# FCCH_RFID_ESTOP.net
KiCad netlist of a schematic drawn in EAGLE
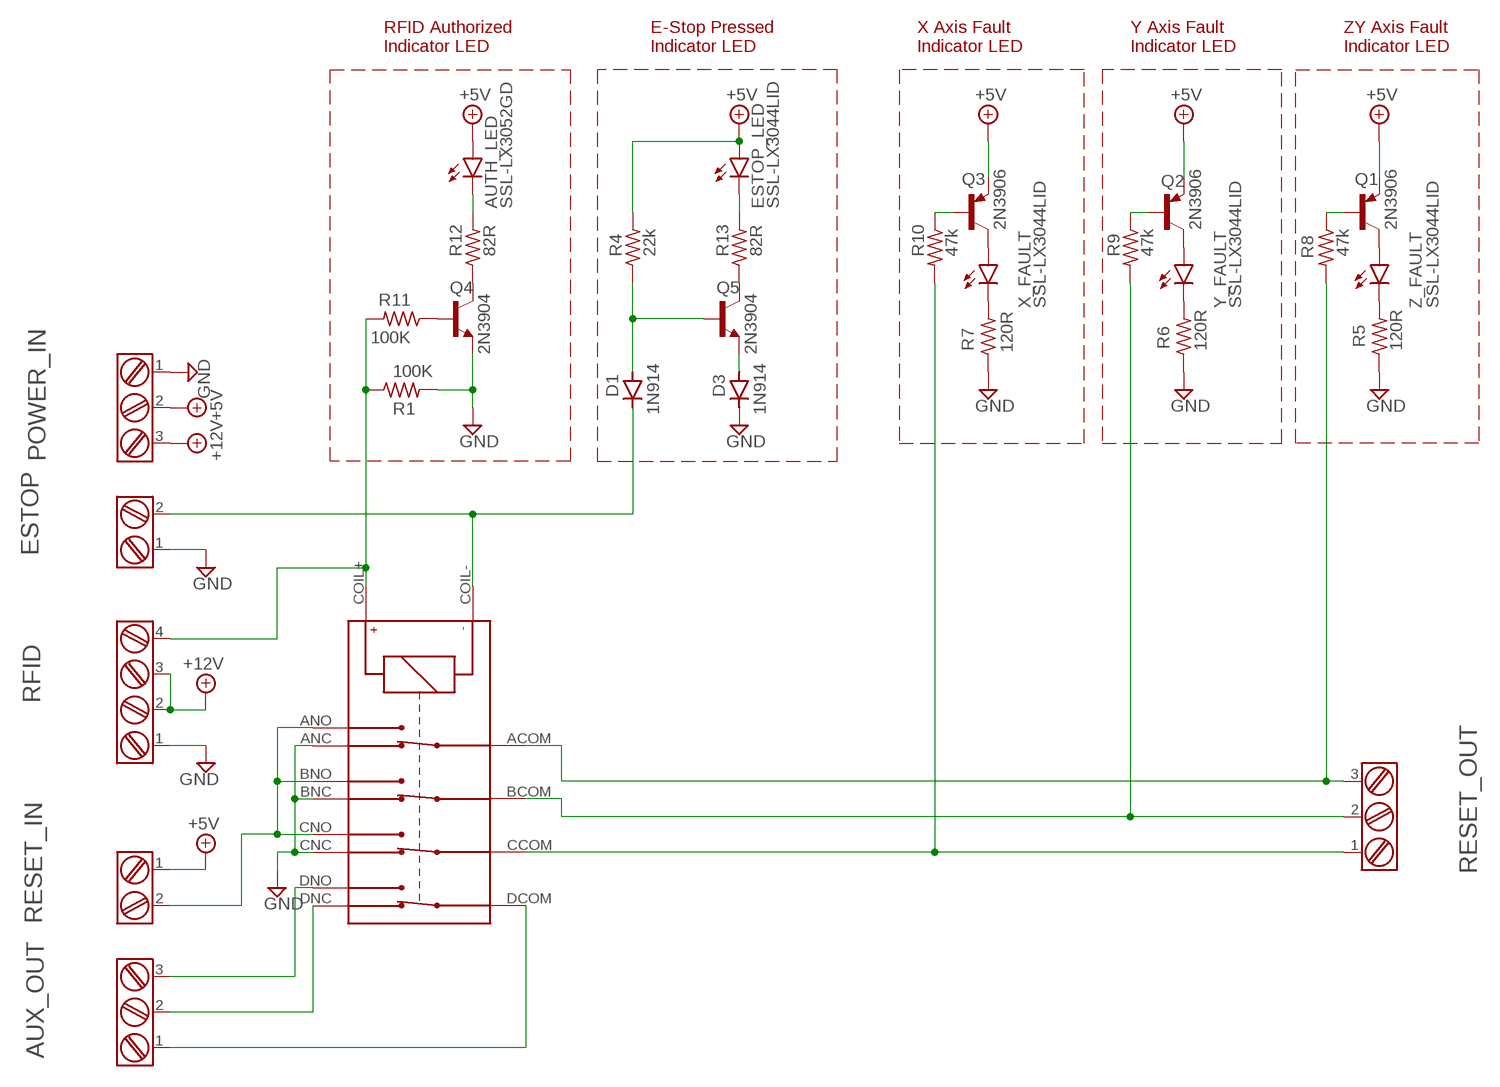
[diagram p0: schematic, sheet 1]

(export (version "E")
  (design (tool "Eeschema 10.0.6"))
  (components
    (comp (ref "AUTH_LED")
      (value "SSL-LX3052GD")
      (footprint "eagle-import:LED3MM")
      (libsource (lib "eagle-import") (part "LED3MM"))
    )
    (comp (ref "AUX_OUT")
      (value "EURO-CON-3_2.54P")
      (footprint "eagle-import:CONN3-2.54P")
      (fields
        (field (name "DIGIKEY_PART_NUMBER") "A98334-ND")
        (field (name "MF") "TE")
        (field (name "MOUSER_PART_NUMBER") "571-2828343")
      )
      (libsource (lib "eagle-import") (part "EURO-CON-3_2.54P"))
    )
    (comp (ref "D1")
      (value "1N914")
      (footprint "eagle-import:D-5")
      (libsource (lib "eagle-import") (part "DIODE-D-5"))
    )
    (comp (ref "D3")
      (value "1N914")
      (footprint "eagle-import:D-5")
      (libsource (lib "eagle-import") (part "DIODE-D-5"))
    )
    (comp (ref "ESTOP")
      (value "EURO-CON-2_2.54P")
      (footprint "eagle-import:CONN2_2.54P")
      (fields
        (field (name "DIGIKEY_PART_NUMBER") "A98333-ND")
        (field (name "MF") "TE")
        (field (name "MOUSER_PART_NUMBER") "571-282834-2")
      )
      (libsource (lib "eagle-import") (part "EURO-CON-2_2.54P"))
    )
    (comp (ref "ESTOP_LED")
      (value "SSL-LX3044LID")
      (footprint "eagle-import:LED3MM")
      (libsource (lib "eagle-import") (part "LED3MM"))
    )
    (comp (ref "POWER_IN")
      (value "EURO-CON-3_2.54P")
      (footprint "eagle-import:CONN3-2.54P")
      (fields
        (field (name "DIGIKEY_PART_NUMBER") "A98334-ND")
        (field (name "MF") "TE")
        (field (name "MOUSER_PART_NUMBER") "571-2828343")
      )
      (libsource (lib "eagle-import") (part "EURO-CON-3_2.54P"))
    )
    (comp (ref "Q1")
      (value "2N3906")
      (footprint "eagle-import:TO92")
      (libsource (lib "eagle-import") (part "2N3906"))
    )
    (comp (ref "Q2")
      (value "2N3906")
      (footprint "eagle-import:TO92")
      (libsource (lib "eagle-import") (part "2N3906"))
    )
    (comp (ref "Q3")
      (value "2N3906")
      (footprint "eagle-import:TO92")
      (libsource (lib "eagle-import") (part "2N3906"))
    )
    (comp (ref "Q4")
      (value "2N3904")
      (footprint "eagle-import:TO92")
      (libsource (lib "eagle-import") (part "2N3904"))
    )
    (comp (ref "Q5")
      (value "2N3904")
      (footprint "eagle-import:TO92")
      (libsource (lib "eagle-import") (part "2N3904"))
    )
    (comp (ref "R1")
      (value "100K")
      (footprint "eagle-import:0204_7")
      (libsource (lib "eagle-import") (part "R-US_0204/7"))
    )
    (comp (ref "R4")
      (value "22k")
      (footprint "eagle-import:0204_7")
      (libsource (lib "eagle-import") (part "R-US_0204/7"))
    )
    (comp (ref "R5")
      (value "120R")
      (footprint "eagle-import:0204_7")
      (libsource (lib "eagle-import") (part "R-US_0204/7"))
    )
    (comp (ref "R6")
      (value "120R")
      (footprint "eagle-import:0204_7")
      (libsource (lib "eagle-import") (part "R-US_0204/7"))
    )
    (comp (ref "R7")
      (value "120R")
      (footprint "eagle-import:0204_7")
      (libsource (lib "eagle-import") (part "R-US_0204/7"))
    )
    (comp (ref "R8")
      (value "47k")
      (footprint "eagle-import:0204_7")
      (libsource (lib "eagle-import") (part "R-US_0204/7"))
    )
    (comp (ref "R9")
      (value "47k")
      (footprint "eagle-import:0204_7")
      (libsource (lib "eagle-import") (part "R-US_0204/7"))
    )
    (comp (ref "R10")
      (value "47k")
      (footprint "eagle-import:0204_7")
      (libsource (lib "eagle-import") (part "R-US_0204/7"))
    )
    (comp (ref "R11")
      (value "100K")
      (footprint "eagle-import:0204_7")
      (libsource (lib "eagle-import") (part "R-US_0204/7"))
    )
    (comp (ref "R12")
      (value "82R")
      (footprint "eagle-import:0204_7")
      (libsource (lib "eagle-import") (part "R-US_0204/7"))
    )
    (comp (ref "R13")
      (value "82R")
      (footprint "eagle-import:0204_7")
      (libsource (lib "eagle-import") (part "R-US_0204/7"))
    )
    (comp (ref "RESET_IN")
      (value "EURO-CON-2_2.54P")
      (footprint "eagle-import:CONN2_2.54P")
      (fields
        (field (name "DIGIKEY_PART_NUMBER") "A98333-ND")
        (field (name "MF") "TE")
        (field (name "MOUSER_PART_NUMBER") "571-282834-2")
      )
      (libsource (lib "eagle-import") (part "EURO-CON-2_2.54P"))
    )
    (comp (ref "RESET_OUT")
      (value "EURO-CON-3_2.54P")
      (footprint "eagle-import:CONN3-2.54P")
      (fields
        (field (name "DIGIKEY_PART_NUMBER") "A98334-ND")
        (field (name "MF") "TE")
        (field (name "MOUSER_PART_NUMBER") "571-2828343")
      )
      (libsource (lib "eagle-import") (part "EURO-CON-3_2.54P"))
    )
    (comp (ref "RFID")
      (value "EURO-CON-4_2.54P")
      (footprint "eagle-import:CONN4-2.54P")
      (fields
        (field (name "DIGIKEY_PART_NUMBER") "A98335-ND")
        (field (name "MF") "TE")
        (field (name "MOUSER_PART_NUMBER") "571-282834-4")
      )
      (libsource (lib "eagle-import") (part "EURO-CON-4_2.54P"))
    )
    (comp (ref "U$1")
      (value "NC4D-JP-DC5V")
      (footprint "eagle-import:NC4D-JP")
      (libsource (lib "eagle-import") (part "NC4D-JP-DC5V"))
    )
    (comp (ref "X_FAULT")
      (value "SSL-LX3044LID")
      (footprint "eagle-import:LED3MM")
      (libsource (lib "eagle-import") (part "LED3MM"))
    )
    (comp (ref "Y_FAULT")
      (value "SSL-LX3044LID")
      (footprint "eagle-import:LED3MM")
      (libsource (lib "eagle-import") (part "LED3MM"))
    )
    (comp (ref "Z_FAULT")
      (value "SSL-LX3044LID")
      (footprint "eagle-import:LED3MM")
      (libsource (lib "eagle-import") (part "LED3MM"))
    )
  )
  (nets
    (net (code "1") (name "+5V") (class "Default")
      (node (ref "AUTH_LED") (pin "A") (pinfunction "A_A") (pintype "passive"))
      (node (ref "ESTOP_LED") (pin "A") (pinfunction "A_A") (pintype "passive"))
      (node (ref "POWER_IN") (pin "2") (pinfunction "2_2") (pintype "bidirectional"))
      (node (ref "Q1") (pin "3") (pinfunction "E_3") (pintype "passive"))
      (node (ref "Q2") (pin "3") (pinfunction "E_3") (pintype "passive"))
      (node (ref "Q3") (pin "3") (pinfunction "E_3") (pintype "passive"))
      (node (ref "R4") (pin "2") (pinfunction "2_2") (pintype "passive"))
      (node (ref "RESET_IN") (pin "1") (pinfunction "1_1") (pintype "bidirectional"))
    )
    (net (code "2") (name "+12V") (class "Default")
      (node (ref "POWER_IN") (pin "3") (pinfunction "3_3") (pintype "bidirectional"))
      (node (ref "RFID") (pin "2") (pinfunction "2_2") (pintype "passive"))
      (node (ref "RFID") (pin "3") (pinfunction "3_3") (pintype "passive"))
    )
    (net (code "3") (name "GND") (class "Default")
      (node (ref "D3") (pin "C") (pinfunction "C_C") (pintype "passive"))
      (node (ref "ESTOP") (pin "1") (pinfunction "1_1") (pintype "bidirectional"))
      (node (ref "POWER_IN") (pin "1") (pinfunction "1_1") (pintype "bidirectional"))
      (node (ref "Q4") (pin "3") (pinfunction "E_3") (pintype "passive"))
      (node (ref "R1") (pin "2") (pinfunction "2_2") (pintype "passive"))
      (node (ref "R5") (pin "1") (pinfunction "1_1") (pintype "passive"))
      (node (ref "R6") (pin "1") (pinfunction "1_1") (pintype "passive"))
      (node (ref "R7") (pin "1") (pinfunction "1_1") (pintype "passive"))
      (node (ref "RFID") (pin "1") (pinfunction "1_1") (pintype "passive"))
      (node (ref "U$1") (pin "ANC") (pinfunction "ANC_ANC") (pintype "bidirectional"))
      (node (ref "U$1") (pin "BNC") (pinfunction "BNC_BNC") (pintype "bidirectional"))
      (node (ref "U$1") (pin "CNC") (pinfunction "CNC_CNC") (pintype "bidirectional"))
    )
    (net (code "4") (name "Net-(AUTH_LED-C)") (class "Default")
      (node (ref "AUTH_LED") (pin "K") (pinfunction "C_K") (pintype "passive"))
      (node (ref "R12") (pin "2") (pinfunction "2_2") (pintype "passive"))
    )
    (net (code "5") (name "Net-(AUX_OUT-Pad1)") (class "Default")
      (node (ref "AUX_OUT") (pin "1") (pinfunction "1_1") (pintype "bidirectional"))
      (node (ref "U$1") (pin "DCOM") (pinfunction "DCOM_DCOM") (pintype "bidirectional"))
    )
    (net (code "6") (name "Net-(AUX_OUT-Pad2)") (class "Default")
      (node (ref "AUX_OUT") (pin "2") (pinfunction "2_2") (pintype "bidirectional"))
      (node (ref "U$1") (pin "DNC") (pinfunction "DNC_DNC") (pintype "bidirectional"))
    )
    (net (code "7") (name "Net-(AUX_OUT-Pad3)") (class "Default")
      (node (ref "AUX_OUT") (pin "3") (pinfunction "3_3") (pintype "bidirectional"))
      (node (ref "U$1") (pin "DNO") (pinfunction "DNO_DNO") (pintype "bidirectional"))
    )
    (net (code "8") (name "Net-(D1-PadC)") (class "Default")
      (node (ref "D1") (pin "C") (pinfunction "C_C") (pintype "passive"))
      (node (ref "ESTOP") (pin "2") (pinfunction "2_2") (pintype "bidirectional"))
      (node (ref "U$1") (pin "COIL-") (pinfunction "COIL-_COIL-") (pintype "bidirectional"))
    )
    (net (code "9") (name "Net-(ESTOP_LED-C)") (class "Default")
      (node (ref "ESTOP_LED") (pin "K") (pinfunction "C_K") (pintype "passive"))
      (node (ref "R13") (pin "2") (pinfunction "2_2") (pintype "passive"))
    )
    (net (code "10") (name "Net-(Q1-B)") (class "Default")
      (node (ref "Q1") (pin "2") (pinfunction "B_2") (pintype "passive"))
      (node (ref "R8") (pin "1") (pinfunction "1_1") (pintype "passive"))
    )
    (net (code "11") (name "Net-(Q1-C)") (class "Default")
      (node (ref "Q1") (pin "1") (pinfunction "C_1") (pintype "passive"))
      (node (ref "Z_FAULT") (pin "A") (pinfunction "A_A") (pintype "passive"))
    )
    (net (code "12") (name "Net-(Q2-B)") (class "Default")
      (node (ref "Q2") (pin "2") (pinfunction "B_2") (pintype "passive"))
      (node (ref "R9") (pin "1") (pinfunction "1_1") (pintype "passive"))
    )
    (net (code "13") (name "Net-(Q2-C)") (class "Default")
      (node (ref "Q2") (pin "1") (pinfunction "C_1") (pintype "passive"))
      (node (ref "Y_FAULT") (pin "A") (pinfunction "A_A") (pintype "passive"))
    )
    (net (code "14") (name "Net-(Q3-B)") (class "Default")
      (node (ref "Q3") (pin "2") (pinfunction "B_2") (pintype "passive"))
      (node (ref "R10") (pin "1") (pinfunction "1_1") (pintype "passive"))
    )
    (net (code "15") (name "Net-(Q3-C)") (class "Default")
      (node (ref "Q3") (pin "1") (pinfunction "C_1") (pintype "passive"))
      (node (ref "X_FAULT") (pin "A") (pinfunction "A_A") (pintype "passive"))
    )
    (net (code "16") (name "Net-(Q4-B)") (class "Default")
      (node (ref "Q4") (pin "2") (pinfunction "B_2") (pintype "passive"))
      (node (ref "R11") (pin "1") (pinfunction "1_1") (pintype "passive"))
    )
    (net (code "17") (name "Net-(Q4-C)") (class "Default")
      (node (ref "Q4") (pin "1") (pinfunction "C_1") (pintype "passive"))
      (node (ref "R12") (pin "1") (pinfunction "1_1") (pintype "passive"))
    )
    (net (code "18") (name "Net-(Q5-B)") (class "Default")
      (node (ref "D1") (pin "A") (pinfunction "A_A") (pintype "passive"))
      (node (ref "Q5") (pin "2") (pinfunction "B_2") (pintype "passive"))
      (node (ref "R4") (pin "1") (pinfunction "1_1") (pintype "passive"))
    )
    (net (code "19") (name "Net-(Q5-C)") (class "Default")
      (node (ref "Q5") (pin "1") (pinfunction "C_1") (pintype "passive"))
      (node (ref "R13") (pin "1") (pinfunction "1_1") (pintype "passive"))
    )
    (net (code "20") (name "Net-(Q5-E)") (class "Default")
      (node (ref "D3") (pin "A") (pinfunction "A_A") (pintype "passive"))
      (node (ref "Q5") (pin "3") (pinfunction "E_3") (pintype "passive"))
    )
    (net (code "21") (name "Net-(R1-Pad1)") (class "Default")
      (node (ref "R1") (pin "1") (pinfunction "1_1") (pintype "passive"))
      (node (ref "R11") (pin "2") (pinfunction "2_2") (pintype "passive"))
      (node (ref "RFID") (pin "4") (pinfunction "4_4") (pintype "passive"))
      (node (ref "U$1") (pin "COIL+") (pinfunction "COIL+_COIL+") (pintype "bidirectional"))
    )
    (net (code "22") (name "Net-(R8-Pad2)") (class "Default")
      (node (ref "R8") (pin "2") (pinfunction "2_2") (pintype "passive"))
      (node (ref "RESET_OUT") (pin "3") (pinfunction "3_3") (pintype "bidirectional"))
      (node (ref "U$1") (pin "ACOM") (pinfunction "ACOM_ACOM") (pintype "bidirectional"))
    )
    (net (code "23") (name "Net-(R9-Pad2)") (class "Default")
      (node (ref "R9") (pin "2") (pinfunction "2_2") (pintype "passive"))
      (node (ref "RESET_OUT") (pin "2") (pinfunction "2_2") (pintype "bidirectional"))
      (node (ref "U$1") (pin "BCOM") (pinfunction "BCOM_BCOM") (pintype "bidirectional"))
    )
    (net (code "24") (name "Net-(R10-Pad2)") (class "Default")
      (node (ref "R10") (pin "2") (pinfunction "2_2") (pintype "passive"))
      (node (ref "RESET_OUT") (pin "1") (pinfunction "1_1") (pintype "bidirectional"))
      (node (ref "U$1") (pin "CCOM") (pinfunction "CCOM_CCOM") (pintype "bidirectional"))
    )
    (net (code "25") (name "Net-(RESET_IN-Pad2)") (class "Default")
      (node (ref "RESET_IN") (pin "2") (pinfunction "2_2") (pintype "bidirectional"))
      (node (ref "U$1") (pin "ANO") (pinfunction "ANO_ANO") (pintype "bidirectional"))
      (node (ref "U$1") (pin "BNO") (pinfunction "BNO_BNO") (pintype "bidirectional"))
      (node (ref "U$1") (pin "CNO") (pinfunction "CNO_CNO") (pintype "bidirectional"))
    )
    (net (code "26") (name "Net-(X_FAULT-C)") (class "Default")
      (node (ref "R7") (pin "2") (pinfunction "2_2") (pintype "passive"))
      (node (ref "X_FAULT") (pin "K") (pinfunction "C_K") (pintype "passive"))
    )
    (net (code "27") (name "Net-(Y_FAULT-C)") (class "Default")
      (node (ref "R6") (pin "2") (pinfunction "2_2") (pintype "passive"))
      (node (ref "Y_FAULT") (pin "K") (pinfunction "C_K") (pintype "passive"))
    )
    (net (code "28") (name "Net-(Z_FAULT-C)") (class "Default")
      (node (ref "R5") (pin "2") (pinfunction "2_2") (pintype "passive"))
      (node (ref "Z_FAULT") (pin "K") (pinfunction "C_K") (pintype "passive"))
    )
  )
)
